# Cap_Array_100p_16u.net
KiCad netlist of a schematic drawn in Altium Designer
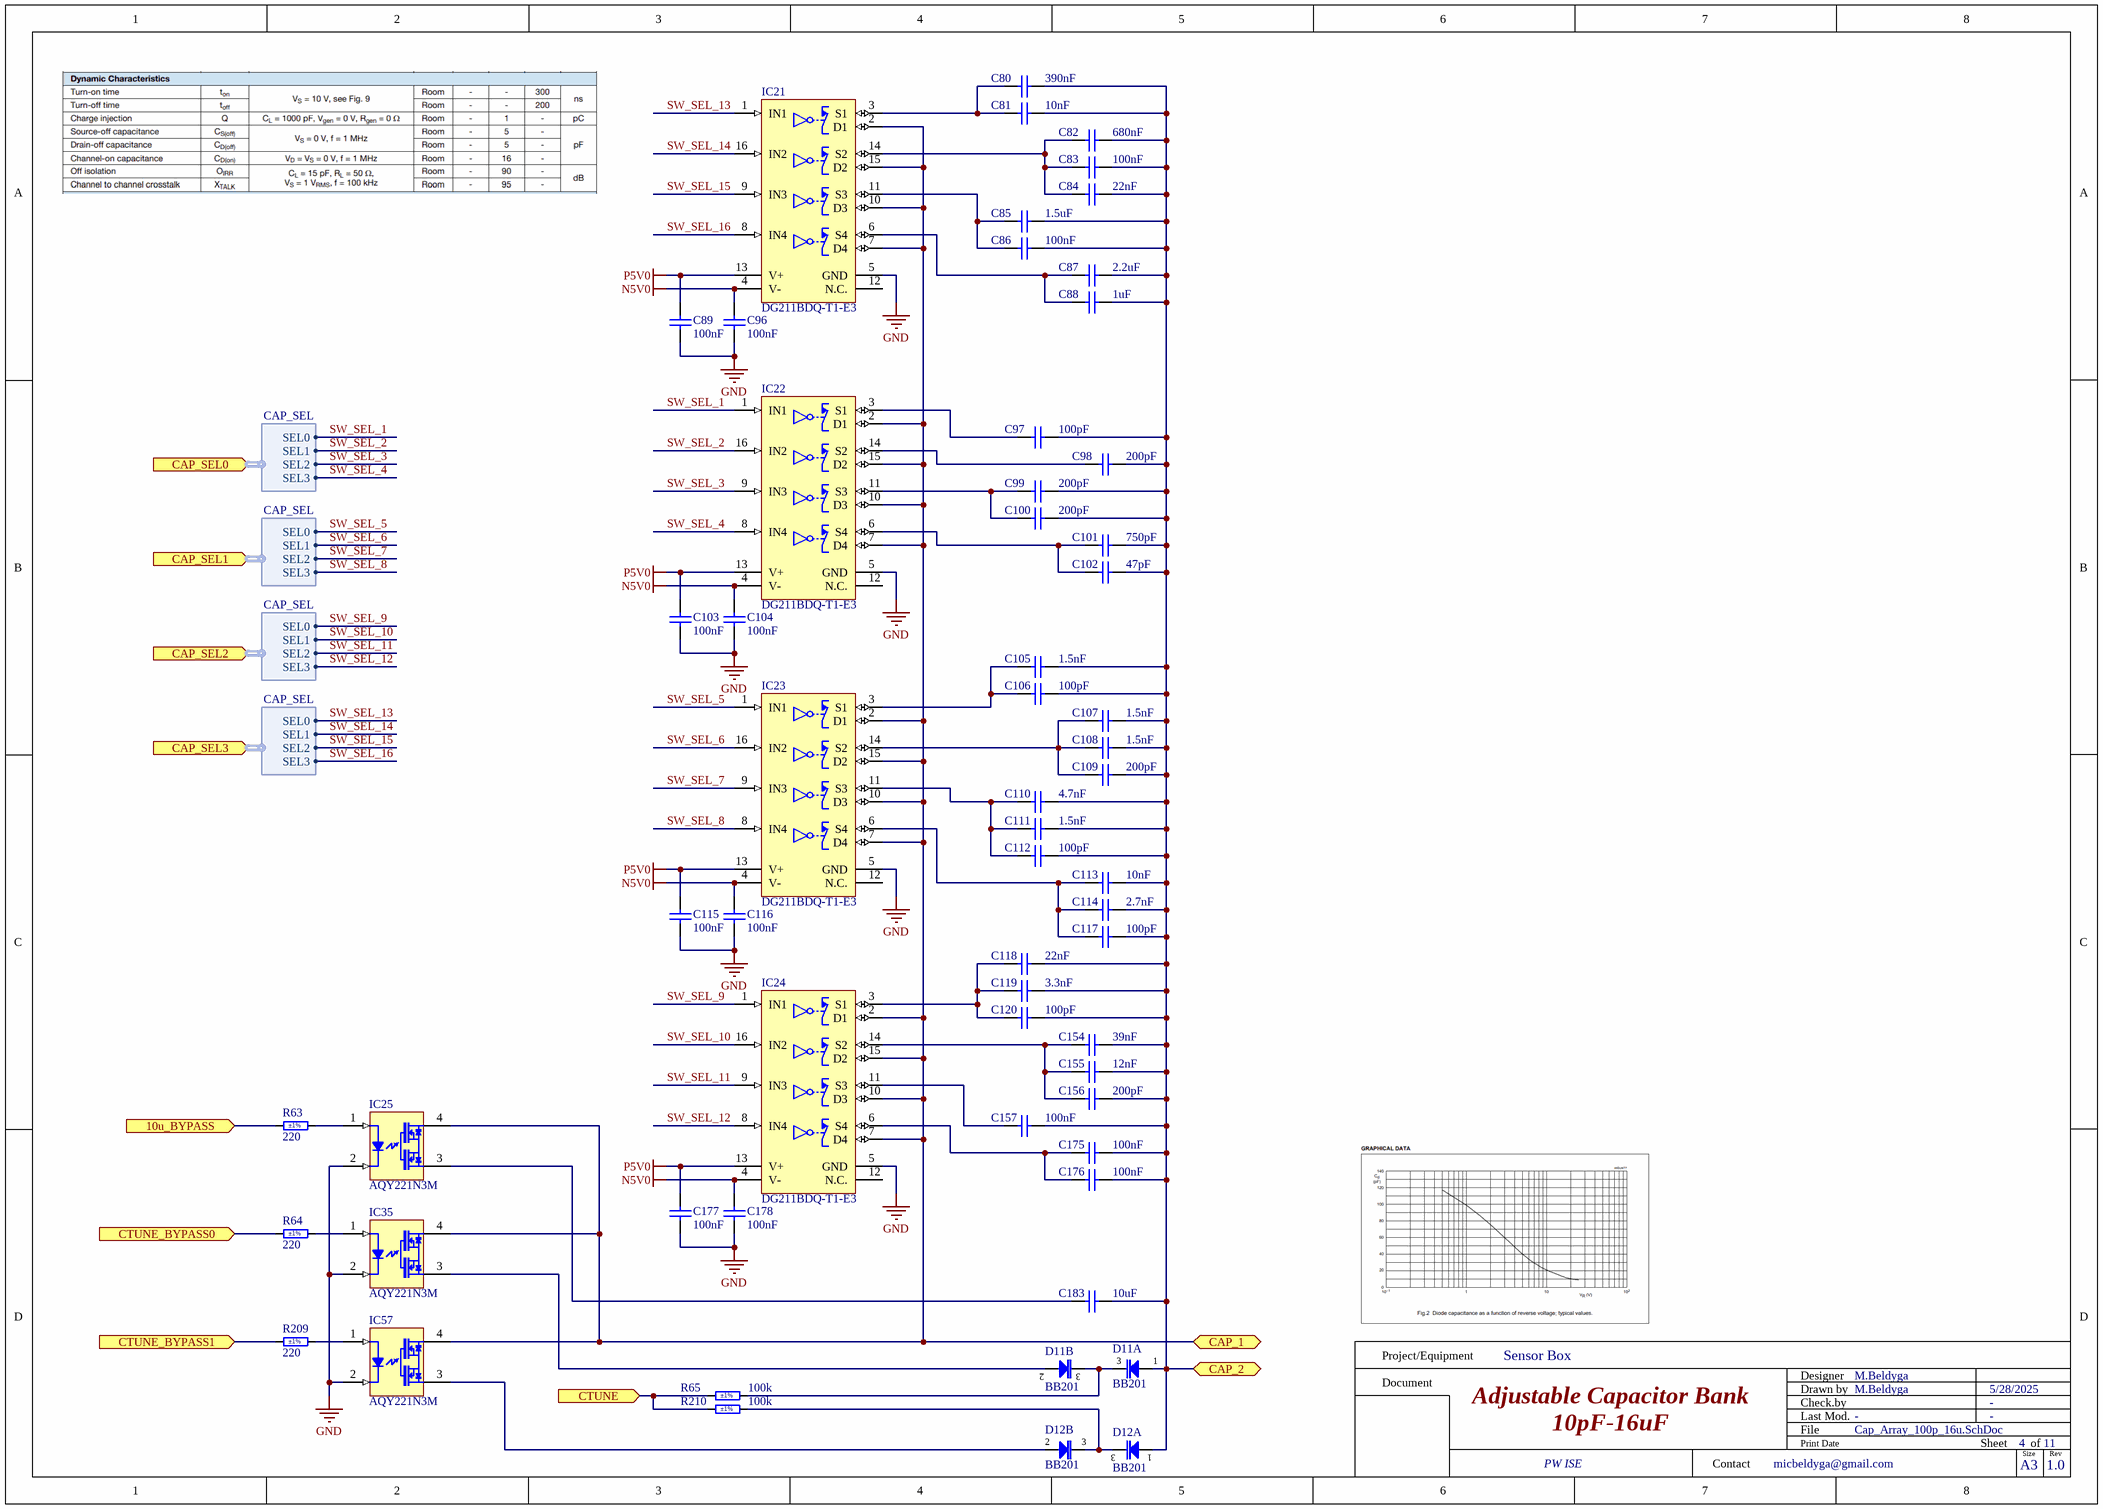
[diagram p0: Cap_Array_100p_16u.SchDoc]

(export (version "E")
  (design (tool "Eeschema 10.0.6"))
  (components
    (comp (ref "C80")
      (value "390nF")
      (footprint "CAPC1608X90N")
      (description "Cap Ceramic 0.39uF 16V X7R 5% Pad SMD 0603 125C T/R")
      (fields
        (field (name "MANUFACTURER") "KEMET")
        (field (name "MANUFACTURER PART NUMBER") "C0603C394J4RACTU")
      )
      (libsource (lib "mb") (part "0603 390nF 16V"))
    )
    (comp (ref "C81")
      (value "10nF")
      (footprint "CAPC1005X55N")
      (description "Non-polarised capacitor")
      (fields
        (field (name "PART NUMBER") "CC0402_10NF_16V_10%_X7R")
        (field (name "VOLTAGE") "16V")
        (field (name "AUTHOR") "CERN DEM JLC")
      )
      (libsource (lib "Capacitors") (part "Capacitor - non polarized"))
    )
    (comp (ref "C82")
      (value "680nF")
      (footprint "CAPC1608X90N")
      (description "Surface Mount Ceramic Multilayer Capacitor 0.68uF 5% X7R 16V 0603 Paper T/R")
      (fields
        (field (name "MANUFACTURER") "Yageo")
        (field (name "MANUFACTURER PART NUMBER") "CC0603JRX7R7BB684")
      )
      (libsource (lib "mb") (part "0603 680nF 16V"))
    )
    (comp (ref "C83")
      (value "100nF")
      (footprint "CAPC1005X55N")
      (description "Non-polarised capacitor")
      (fields
        (field (name "PART NUMBER") "CC0402_100NF_50V_10%_X7R")
        (field (name "VOLTAGE") "50V")
        (field (name "AUTHOR") "CERN DEM MR")
      )
      (libsource (lib "Capacitors") (part "Capacitor - non polarized"))
    )
    (comp (ref "C84")
      (value "22nF")
      (footprint "CAPC1005X55N")
      (description "Non-polarised capacitor")
      (fields
        (field (name "PART NUMBER") "CC0402_22NF_50V_5%_X7R")
        (field (name "VOLTAGE") "50V")
        (field (name "AUTHOR") "CERN DEM BC")
      )
      (libsource (lib "Capacitors") (part "Capacitor - non polarized"))
    )
    (comp (ref "C85")
      (value "1.5uF")
      (footprint "CAPC2012X95N")
      (description "Multilayer Ceramic Capacitors MLCC - SMD/SMT 16V 1.5uF X7R 0805 5% AEC-Q200")
      (fields
        (field (name "MANUFACTURER") "KEMET")
        (field (name "MANUFACTURER PART NUMBER") "C0805C155J4RECAUTO")
      )
      (libsource (lib "mb") (part "0805 1.5uF 16V"))
    )
    (comp (ref "C86")
      (value "100nF")
      (footprint "CAPC1005X55N")
      (description "Non-polarised capacitor")
      (fields
        (field (name "PART NUMBER") "CC0402_100NF_50V_10%_X7R")
        (field (name "VOLTAGE") "50V")
        (field (name "AUTHOR") "CERN DEM MR")
      )
      (libsource (lib "Capacitors") (part "Capacitor - non polarized"))
    )
    (comp (ref "C87")
      (value "2.2uF")
      (footprint "CAPC2012X95N")
      (fields
        (field (name "MANUFACTURER") "KEMET")
        (field (name "MANUFACTURER PART NUMBER") "C0805C225J4RECTU")
      )
      (libsource (lib "mb") (part "0805 2.2uF 16V"))
    )
    (comp (ref "C88")
      (value "1uF")
      (footprint "CAPC1608X90N")
      (description "SMD Multilayer Ceramic Capacitor, 1 ï¿½F, 16 V, 0603 [1608 Metric], ï¿½ 5%, X7R")
      (fields
        (field (name "MANUFACTURER") "Yageo")
        (field (name "MANUFACTURER PART NUMBER") "CC0603JRX7R7BB105")
      )
      (libsource (lib "mb") (part "0603 1uF 16V"))
    )
    (comp (ref "C89")
      (value "100nF")
      (footprint "CAPC1005X55N")
      (description "Non-polarised capacitor")
      (fields
        (field (name "PART NUMBER") "CC0402_100NF_50V_10%_X7R")
        (field (name "VOLTAGE") "50V")
        (field (name "AUTHOR") "CERN DEM MR")
      )
      (libsource (lib "Capacitors") (part "Capacitor - non polarized"))
    )
    (comp (ref "C96")
      (value "100nF")
      (footprint "CAPC1005X55N")
      (description "Non-polarised capacitor")
      (fields
        (field (name "PART NUMBER") "CC0402_100NF_50V_10%_X7R")
        (field (name "VOLTAGE") "50V")
        (field (name "AUTHOR") "CERN DEM MR")
      )
      (libsource (lib "Capacitors") (part "Capacitor - non polarized"))
    )
    (comp (ref "C97")
      (value "100pF")
      (footprint "CAPC1005X55N")
      (description "Non-polarised capacitor")
      (fields
        (field (name "PART NUMBER") "CC0402_100PF_25V_1%_C0G")
        (field (name "VOLTAGE") "25V")
        (field (name "AUTHOR") "CERN DEM HF")
      )
      (libsource (lib "Capacitors") (part "Capacitor - non polarized"))
    )
    (comp (ref "C98")
      (value "200pF")
      (footprint "CAPC1005X55N")
      (description "Multilayer Ceramic Capacitor, 200 pF, 50 V, ï¿½ 1%, C0G (NP0), 0402 [1005 Metric]")
      (fields
        (field (name "MANUFACTURER") "Murata")
        (field (name "MANUFACTURER PART NUMBER") "GCM1555C1H201FA16D")
      )
      (libsource (lib "mb") (part "0402 200pF 50V"))
    )
    (comp (ref "C99")
      (value "200pF")
      (footprint "CAPC1005X55N")
      (description "Multilayer Ceramic Capacitor, 200 pF, 50 V, ï¿½ 1%, C0G (NP0), 0402 [1005 Metric]")
      (fields
        (field (name "MANUFACTURER") "Murata")
        (field (name "MANUFACTURER PART NUMBER") "GCM1555C1H201FA16D")
      )
      (libsource (lib "mb") (part "0402 200pF 50V"))
    )
    (comp (ref "C100")
      (value "200pF")
      (footprint "CAPC1005X55N")
      (description "Multilayer Ceramic Capacitor, 200 pF, 50 V, ï¿½ 1%, C0G (NP0), 0402 [1005 Metric]")
      (fields
        (field (name "MANUFACTURER") "Murata")
        (field (name "MANUFACTURER PART NUMBER") "GCM1555C1H201FA16D")
      )
      (libsource (lib "mb") (part "0402 200pF 50V"))
    )
    (comp (ref "C101")
      (value "750pF")
      (footprint "CAPC1005X55N")
      (description "Cap Auto-grade 750PF 50VDC C0G 1% SMD 0402")
      (fields
        (field (name "MANUFACTURER") "Murata")
        (field (name "MANUFACTURER PART NUMBER") "GCM1555C1H751FA16D")
      )
      (libsource (lib "mb") (part "0402 750pF 50V"))
    )
    (comp (ref "C102")
      (value "47pF")
      (footprint "CAPC1005X55N")
      (description "Non-polarised capacitor")
      (fields
        (field (name "PART NUMBER") "CC0402_47PF_50V_1%_C0G_MURATA_GJM1555C1H470FB01D")
        (field (name "VOLTAGE") "50V")
        (field (name "AUTHOR") "CERN DEM BC")
      )
      (libsource (lib "Capacitors") (part "Capacitor - non polarized"))
    )
    (comp (ref "C103")
      (value "100nF")
      (footprint "CAPC1005X55N")
      (description "Non-polarised capacitor")
      (fields
        (field (name "PART NUMBER") "CC0402_100NF_50V_10%_X7R")
        (field (name "VOLTAGE") "50V")
        (field (name "AUTHOR") "CERN DEM MR")
      )
      (libsource (lib "Capacitors") (part "Capacitor - non polarized"))
    )
    (comp (ref "C104")
      (value "100nF")
      (footprint "CAPC1005X55N")
      (description "Non-polarised capacitor")
      (fields
        (field (name "PART NUMBER") "CC0402_100NF_50V_10%_X7R")
        (field (name "VOLTAGE") "50V")
        (field (name "AUTHOR") "CERN DEM MR")
      )
      (libsource (lib "Capacitors") (part "Capacitor - non polarized"))
    )
    (comp (ref "C105")
      (value "1.5nF")
      (footprint "CAPC1005X55N")
      (fields
        (field (name "MANUFACTURER") "KEMET")
        (field (name "MANUFACTURER PART NUMBER") "C0402C152F5GECAUTO")
      )
      (libsource (lib "mb") (part "0402 1.5nF 50V"))
    )
    (comp (ref "C106")
      (value "100pF")
      (footprint "CAPC1005X55N")
      (description "Non-polarised capacitor")
      (fields
        (field (name "PART NUMBER") "CC0402_100PF_25V_1%_C0G")
        (field (name "VOLTAGE") "25V")
        (field (name "AUTHOR") "CERN DEM HF")
      )
      (libsource (lib "Capacitors") (part "Capacitor - non polarized"))
    )
    (comp (ref "C107")
      (value "1.5nF")
      (footprint "CAPC1005X55N")
      (fields
        (field (name "MANUFACTURER") "KEMET")
        (field (name "MANUFACTURER PART NUMBER") "C0402C152F5GECAUTO")
      )
      (libsource (lib "mb") (part "0402 1.5nF 50V"))
    )
    (comp (ref "C108")
      (value "1.5nF")
      (footprint "CAPC1005X55N")
      (fields
        (field (name "MANUFACTURER") "KEMET")
        (field (name "MANUFACTURER PART NUMBER") "C0402C152F5GECAUTO")
      )
      (libsource (lib "mb") (part "0402 1.5nF 50V"))
    )
    (comp (ref "C109")
      (value "200pF")
      (footprint "CAPC1005X55N")
      (description "Multilayer Ceramic Capacitor, 200 pF, 50 V, ï¿½ 1%, C0G (NP0), 0402 [1005 Metric]")
      (fields
        (field (name "MANUFACTURER") "Murata")
        (field (name "MANUFACTURER PART NUMBER") "GCM1555C1H201FA16D")
      )
      (libsource (lib "mb") (part "0402 200pF 50V"))
    )
    (comp (ref "C110")
      (value "4.7nF")
      (footprint "CAPC1608X90N")
      (description "Cap Ceramic 0.0047uF 50V C0G 1% Pad SMD 0603 125°C Automotive T/R")
      (fields
        (field (name "MANUFACTURER") "Murata")
        (field (name "MANUFACTURER PART NUMBER") "GCM1885C1H472FA16D")
      )
      (libsource (lib "mb") (part "0603 4.7nF 50V"))
    )
    (comp (ref "C111")
      (value "1.5nF")
      (footprint "CAPC1005X55N")
      (fields
        (field (name "MANUFACTURER") "KEMET")
        (field (name "MANUFACTURER PART NUMBER") "C0402C152F5GECAUTO")
      )
      (libsource (lib "mb") (part "0402 1.5nF 50V"))
    )
    (comp (ref "C112")
      (value "100pF")
      (footprint "CAPC1005X55N")
      (description "Non-polarised capacitor")
      (fields
        (field (name "PART NUMBER") "CC0402_100PF_25V_1%_C0G")
        (field (name "VOLTAGE") "25V")
        (field (name "AUTHOR") "CERN DEM HF")
      )
      (libsource (lib "Capacitors") (part "Capacitor - non polarized"))
    )
    (comp (ref "C113")
      (value "10nF")
      (footprint "CAPC1608X90N")
      (description "Multilayer Ceramic Capacitors MLCC - SMD/SMT 25V 0.01uF C0G 0603 1% AEC-Q200")
      (fields
        (field (name "MANUFACTURER") "KEMET")
        (field (name "MANUFACTURER PART NUMBER") "C0603C103F3GECAUTO")
      )
      (libsource (lib "mb") (part "0603 10nF 25V"))
    )
    (comp (ref "C114")
      (value "2.7nF")
      (footprint "CAPC1608X90N")
      (description "Powerrain/Safety for Automotive AEC-Q200 Up to 125C Reflow soldering Flow soldering")
      (fields
        (field (name "MANUFACTURER") "Murata")
        (field (name "MANUFACTURER PART NUMBER") "GCM1885C1H272FA16J")
      )
      (libsource (lib "mb") (part "0603 2.7nF 50V"))
    )
    (comp (ref "C115")
      (value "100nF")
      (footprint "CAPC1005X55N")
      (description "Non-polarised capacitor")
      (fields
        (field (name "PART NUMBER") "CC0402_100NF_50V_10%_X7R")
        (field (name "VOLTAGE") "50V")
        (field (name "AUTHOR") "CERN DEM MR")
      )
      (libsource (lib "Capacitors") (part "Capacitor - non polarized"))
    )
    (comp (ref "C116")
      (value "100nF")
      (footprint "CAPC1005X55N")
      (description "Non-polarised capacitor")
      (fields
        (field (name "PART NUMBER") "CC0402_100NF_50V_10%_X7R")
        (field (name "VOLTAGE") "50V")
        (field (name "AUTHOR") "CERN DEM MR")
      )
      (libsource (lib "Capacitors") (part "Capacitor - non polarized"))
    )
    (comp (ref "C117")
      (value "100pF")
      (footprint "CAPC1005X55N")
      (description "Non-polarised capacitor")
      (fields
        (field (name "PART NUMBER") "CC0402_100PF_25V_1%_C0G")
        (field (name "VOLTAGE") "25V")
        (field (name "AUTHOR") "CERN DEM HF")
      )
      (libsource (lib "Capacitors") (part "Capacitor - non polarized"))
    )
    (comp (ref "C118")
      (value "22nF")
      (footprint "CAPC2012X95N")
      (description "0805 50V C0G 0.022uF 1% Automotive grade multilayer ceramic capacitor")
      (fields
        (field (name "MANUFACTURER") "Murata")
        (field (name "MANUFACTURER PART NUMBER") "GCM21B5C1H223FA16L")
      )
      (libsource (lib "mb") (part "0805 22nF 50V"))
    )
    (comp (ref "C119")
      (value "3.3nF")
      (footprint "CAPC1608X90N")
      (description "Cap Ceramic 0.0033uF 50V C0G 1% Pad SMD 0603 125°C Automotive T/R")
      (fields
        (field (name "MANUFACTURER") "Murata")
        (field (name "MANUFACTURER PART NUMBER") "GCM1885C1H332FA16D")
      )
      (libsource (lib "mb") (part "0603 3.3nF 50V"))
    )
    (comp (ref "C120")
      (value "100pF")
      (footprint "CAPC1005X55N")
      (description "Non-polarised capacitor")
      (fields
        (field (name "PART NUMBER") "CC0402_100PF_25V_1%_C0G")
        (field (name "VOLTAGE") "25V")
        (field (name "AUTHOR") "CERN DEM HF")
      )
      (libsource (lib "Capacitors") (part "Capacitor - non polarized"))
    )
    (comp (ref "C154")
      (value "39nF")
      (footprint "CAPC2012X95N")
      (description "Multilayer Ceramic Capacitors MLCC - SMD/SMT 0805 C0G 39000pF 2% 100VDC")
      (fields
        (field (name "MANUFACTURER") "Murata")
        (field (name "MANUFACTURER PART NUMBER") "GRM2195C2A393GE01J")
      )
      (libsource (lib "mb") (part "0805 39nF 100V"))
    )
    (comp (ref "C155")
      (value "12nF")
      (footprint "CAPC1608X90N")
      (description "Cap Ceramic 0.012uF 25V C0G 1% Pad SMD 0603 125°C Extreme Low ESR T/R")
      (fields
        (field (name "MANUFACTURER") "KEMET")
        (field (name "MANUFACTURER PART NUMBER") "C0603C123F3GACTU")
      )
      (libsource (lib "mb") (part "0603 12nF 25V"))
    )
    (comp (ref "C156")
      (value "200pF")
      (footprint "CAPC1005X55N")
      (description "Multilayer Ceramic Capacitor, 200 pF, 50 V, ï¿½ 1%, C0G (NP0), 0402 [1005 Metric]")
      (fields
        (field (name "MANUFACTURER") "Murata")
        (field (name "MANUFACTURER PART NUMBER") "GCM1555C1H201FA16D")
      )
      (libsource (lib "mb") (part "0402 200pF 50V"))
    )
    (comp (ref "C157")
      (value "100nF")
      (footprint "CAPC1810X06N")
      (description "Cap Cer 0.1UF 50V C0G/NP0 0704")
      (fields
        (field (name "MANUFACTURER") "Murata")
        (field (name "MANUFACTURER PART NUMBER") "GRMJN65C1H104GE01J")
      )
      (libsource (lib "mb") (part "0704 100nF 50V"))
    )
    (comp (ref "C175")
      (value "100nF")
      (footprint "CAPC1810X06N")
      (description "Cap Cer 0.1UF 50V C0G/NP0 0704")
      (fields
        (field (name "MANUFACTURER") "Murata")
        (field (name "MANUFACTURER PART NUMBER") "GRMJN65C1H104GE01J")
      )
      (libsource (lib "mb") (part "0704 100nF 50V"))
    )
    (comp (ref "C176")
      (value "100nF")
      (footprint "CAPC1810X06N")
      (description "Cap Cer 0.1UF 50V C0G/NP0 0704")
      (fields
        (field (name "MANUFACTURER") "Murata")
        (field (name "MANUFACTURER PART NUMBER") "GRMJN65C1H104GE01J")
      )
      (libsource (lib "mb") (part "0704 100nF 50V"))
    )
    (comp (ref "C177")
      (value "100nF")
      (footprint "CAPC1005X55N")
      (description "Non-polarised capacitor")
      (fields
        (field (name "PART NUMBER") "CC0402_100NF_50V_10%_X7R")
        (field (name "VOLTAGE") "50V")
        (field (name "AUTHOR") "CERN DEM MR")
      )
      (libsource (lib "Capacitors") (part "Capacitor - non polarized"))
    )
    (comp (ref "C178")
      (value "100nF")
      (footprint "CAPC1005X55N")
      (description "Non-polarised capacitor")
      (fields
        (field (name "PART NUMBER") "CC0402_100NF_50V_10%_X7R")
        (field (name "VOLTAGE") "50V")
        (field (name "AUTHOR") "CERN DEM MR")
      )
      (libsource (lib "Capacitors") (part "Capacitor - non polarized"))
    )
    (comp (ref "C183")
      (value "10uF")
      (footprint "CAPC2012X95N")
      (description "Multilayer Ceramic Capacitors MLCC - SMD/SMT 10V 10uF X7R 0805 5% AEC-Q200")
      (fields
        (field (name "MANUFACTURER") "KEMET")
        (field (name "MANUFACTURER PART NUMBER") "C0805C106J8RACAUTO")
      )
      (libsource (lib "mb") (part "0805 10uF 16V"))
    )
    (comp (ref "D11")
      (value "BB201")
      (footprint "SOT95P230X110-3N")
      (description "Dual Common Cathode Varicap Diodes")
      (fields
        (field (name "VOLTAGE") "15V")
        (field (name "POWER") "20mA")
        (field (name "AUTHOR") "CERN DEM JLC")
      )
      (libsource (lib "") (part "Diode Varicap x2 A1C3_A2C3_1"))
    )
    (comp (ref "D12")
      (value "BB201")
      (footprint "SOT95P230X110-3N")
      (description "Dual Common Cathode Varicap Diodes")
      (fields
        (field (name "VOLTAGE") "15V")
        (field (name "POWER") "20mA")
        (field (name "AUTHOR") "CERN DEM JLC")
      )
      (libsource (lib "") (part "Diode Varicap x2 A1C3_A2C3_2"))
    )
    (comp (ref "IC21")
      (value "DG211BDQ-T1-E3")
      (footprint "SOP65P640X120-16N")
      (description "DG211B Series SPST 22 V 50 Ohm Surface Mount Improved Analog Switch - TSSOP-16")
      (fields (field (name "MANUFACTURER") "Vishay Siliconix"))
      (libsource (lib "mb") (part "DG211BDQ-T1-E3"))
    )
    (comp (ref "IC22")
      (value "DG211BDQ-T1-E3")
      (footprint "SOP65P640X120-16N")
      (description "DG211B Series SPST 22 V 50 Ohm Surface Mount Improved Analog Switch - TSSOP-16")
      (fields (field (name "MANUFACTURER") "Vishay Siliconix"))
      (libsource (lib "mb") (part "DG211BDQ-T1-E3"))
    )
    (comp (ref "IC23")
      (value "DG211BDQ-T1-E3")
      (footprint "SOP65P640X120-16N")
      (description "DG211B Series SPST 22 V 50 Ohm Surface Mount Improved Analog Switch - TSSOP-16")
      (fields (field (name "MANUFACTURER") "Vishay Siliconix"))
      (libsource (lib "mb") (part "DG211BDQ-T1-E3"))
    )
    (comp (ref "IC24")
      (value "DG211BDQ-T1-E3")
      (footprint "SOP65P640X120-16N")
      (description "DG211B Series SPST 22 V 50 Ohm Surface Mount Improved Analog Switch - TSSOP-16")
      (fields (field (name "MANUFACTURER") "Vishay Siliconix"))
      (libsource (lib "mb") (part "DG211BDQ-T1-E3"))
    )
    (comp (ref "IC25")
      (value "AQY221N3M")
      (footprint "PANASONIC_AQY22(SON)")
      (description "PhotoMOS Relay")
      (fields (field (name "MANUFACTURER") "PANASONIC") (field (name "AUTHOR") "CERN DEM JLC"))
      (libsource (lib "ICs And Semiconductors") (part "PhotoMOS Relay x1 Type5_a"))
    )
    (comp (ref "IC35")
      (value "AQY221N3M")
      (footprint "PANASONIC_AQY22(SON)")
      (description "PhotoMOS Relay")
      (fields (field (name "MANUFACTURER") "PANASONIC") (field (name "AUTHOR") "CERN DEM JLC"))
      (libsource (lib "ICs And Semiconductors") (part "PhotoMOS Relay x1 Type5_a"))
    )
    (comp (ref "IC57")
      (value "AQY221N3M")
      (footprint "PANASONIC_AQY22(SON)")
      (description "PhotoMOS Relay")
      (fields (field (name "MANUFACTURER") "PANASONIC") (field (name "AUTHOR") "CERN DEM JLC"))
      (libsource (lib "ICs And Semiconductors") (part "PhotoMOS Relay x1 Type5_a"))
    )
    (comp (ref "R63")
      (value "220")
      (footprint "RESC1005X40N")
      (description "Resistor - 1%")
      (fields
        (field (name "TOLERANCE") "±1%")
        (field (name "PART NUMBER") "R0402_220R_1%_0.0625W_100PPM")
        (field (name "POWER") "0.0625W")
        (field (name "AUTHOR") "CERN DEM JLC")
      )
      (libsource (lib "Resistors") (part "Resistor - 1%"))
    )
    (comp (ref "R64")
      (value "220")
      (footprint "RESC1005X40N")
      (description "Resistor - 1%")
      (fields
        (field (name "TOLERANCE") "±1%")
        (field (name "PART NUMBER") "R0402_220R_1%_0.0625W_100PPM")
        (field (name "POWER") "0.0625W")
        (field (name "AUTHOR") "CERN DEM JLC")
      )
      (libsource (lib "Resistors") (part "Resistor - 1%"))
    )
    (comp (ref "R65")
      (value "100k")
      (footprint "RESC1005X40N")
      (description "Resistor - 1%")
      (fields
        (field (name "TOLERANCE") "±1%")
        (field (name "PART NUMBER") "R0402_100K_1%_0.0625W_100PPM")
        (field (name "POWER") "0.0625W")
        (field (name "AUTHOR") "CERN DEM JLC")
      )
      (libsource (lib "Resistors") (part "Resistor - 1%"))
    )
    (comp (ref "R209")
      (value "220")
      (footprint "RESC1005X40N")
      (description "Resistor - 1%")
      (fields
        (field (name "TOLERANCE") "±1%")
        (field (name "PART NUMBER") "R0402_220R_1%_0.0625W_100PPM")
        (field (name "POWER") "0.0625W")
        (field (name "AUTHOR") "CERN DEM JLC")
      )
      (libsource (lib "Resistors") (part "Resistor - 1%"))
    )
    (comp (ref "R210")
      (value "100k")
      (footprint "RESC1005X40N")
      (description "Resistor - 1%")
      (fields
        (field (name "TOLERANCE") "±1%")
        (field (name "PART NUMBER") "R0402_100K_1%_0.0625W_100PPM")
        (field (name "POWER") "0.0625W")
        (field (name "AUTHOR") "CERN DEM JLC")
      )
      (libsource (lib "Resistors") (part "Resistor - 1%"))
    )
  )
  (nets
    (net (code "2") (name "/10u_BYPASS") (class "Default")
      (node (ref "R63") (pin "1") (pinfunction "1_1") (pintype "passive"))
    )
    (net (code "3") (name "/CAP_1") (class "Default")
      (node (ref "IC21") (pin "10") (pinfunction "D3_10") (pintype "bidirectional"))
      (node (ref "IC21") (pin "15") (pinfunction "D2_15") (pintype "bidirectional"))
      (node (ref "IC21") (pin "2") (pinfunction "D1_2") (pintype "bidirectional"))
      (node (ref "IC21") (pin "7") (pinfunction "D4_7") (pintype "bidirectional"))
      (node (ref "IC22") (pin "10") (pinfunction "D3_10") (pintype "bidirectional"))
      (node (ref "IC22") (pin "15") (pinfunction "D2_15") (pintype "bidirectional"))
      (node (ref "IC22") (pin "2") (pinfunction "D1_2") (pintype "bidirectional"))
      (node (ref "IC22") (pin "7") (pinfunction "D4_7") (pintype "bidirectional"))
      (node (ref "IC23") (pin "10") (pinfunction "D3_10") (pintype "bidirectional"))
      (node (ref "IC23") (pin "15") (pinfunction "D2_15") (pintype "bidirectional"))
      (node (ref "IC23") (pin "2") (pinfunction "D1_2") (pintype "bidirectional"))
      (node (ref "IC23") (pin "7") (pinfunction "D4_7") (pintype "bidirectional"))
      (node (ref "IC24") (pin "10") (pinfunction "D3_10") (pintype "bidirectional"))
      (node (ref "IC24") (pin "15") (pinfunction "D2_15") (pintype "bidirectional"))
      (node (ref "IC24") (pin "2") (pinfunction "D1_2") (pintype "bidirectional"))
      (node (ref "IC24") (pin "7") (pinfunction "D4_7") (pintype "bidirectional"))
      (node (ref "IC25") (pin "4") (pinfunction "E_4") (pintype "open_emitter"))
      (node (ref "IC35") (pin "4") (pinfunction "E_4") (pintype "open_emitter"))
      (node (ref "IC57") (pin "4") (pinfunction "E_4") (pintype "open_emitter"))
    )
    (net (code "4") (name "/CAP_2") (class "Default")
      (node (ref "C100") (pin "1") (pinfunction "1_1") (pintype "passive"))
      (node (ref "C101") (pin "1") (pinfunction "1_1") (pintype "passive"))
      (node (ref "C102") (pin "2") (pinfunction "2_2") (pintype "passive"))
      (node (ref "C105") (pin "1") (pinfunction "1_1") (pintype "passive"))
      (node (ref "C106") (pin "2") (pinfunction "2_2") (pintype "passive"))
      (node (ref "C107") (pin "1") (pinfunction "1_1") (pintype "passive"))
      (node (ref "C108") (pin "1") (pinfunction "1_1") (pintype "passive"))
      (node (ref "C109") (pin "1") (pinfunction "1_1") (pintype "passive"))
      (node (ref "C110") (pin "1") (pinfunction "1_1") (pintype "passive"))
      (node (ref "C111") (pin "1") (pinfunction "1_1") (pintype "passive"))
      (node (ref "C112") (pin "2") (pinfunction "2_2") (pintype "passive"))
      (node (ref "C113") (pin "1") (pinfunction "1_1") (pintype "passive"))
      (node (ref "C114") (pin "1") (pinfunction "1_1") (pintype "passive"))
      (node (ref "C117") (pin "2") (pinfunction "2_2") (pintype "passive"))
      (node (ref "C118") (pin "1") (pinfunction "1_1") (pintype "passive"))
      (node (ref "C119") (pin "1") (pinfunction "1_1") (pintype "passive"))
      (node (ref "C120") (pin "2") (pinfunction "2_2") (pintype "passive"))
      (node (ref "C154") (pin "1") (pinfunction "1_1") (pintype "passive"))
      (node (ref "C155") (pin "1") (pinfunction "1_1") (pintype "passive"))
      (node (ref "C156") (pin "1") (pinfunction "1_1") (pintype "passive"))
      (node (ref "C157") (pin "1") (pinfunction "1_1") (pintype "passive"))
      (node (ref "C175") (pin "1") (pinfunction "1_1") (pintype "passive"))
      (node (ref "C176") (pin "1") (pinfunction "1_1") (pintype "passive"))
      (node (ref "C183") (pin "1") (pinfunction "1_1") (pintype "passive"))
      (node (ref "C80") (pin "1") (pinfunction "1_1") (pintype "passive"))
      (node (ref "C81") (pin "2") (pinfunction "2_2") (pintype "passive"))
      (node (ref "C82") (pin "1") (pinfunction "1_1") (pintype "passive"))
      (node (ref "C83") (pin "1") (pinfunction "1_1") (pintype "passive"))
      (node (ref "C84") (pin "2") (pinfunction "2_2") (pintype "passive"))
      (node (ref "C85") (pin "1") (pinfunction "1_1") (pintype "passive"))
      (node (ref "C86") (pin "1") (pinfunction "1_1") (pintype "passive"))
      (node (ref "C87") (pin "1") (pinfunction "1_1") (pintype "passive"))
      (node (ref "C88") (pin "1") (pinfunction "1_1") (pintype "passive"))
      (node (ref "C97") (pin "2") (pinfunction "2_2") (pintype "passive"))
      (node (ref "C98") (pin "1") (pinfunction "1_1") (pintype "passive"))
      (node (ref "C99") (pin "1") (pinfunction "1_1") (pintype "passive"))
      (node (ref "D11") (pin "1") (pinfunction "A_1") (pintype "passive"))
      (node (ref "D12") (pin "1") (pinfunction "A_1") (pintype "passive"))
    )
    (net (code "5") (name "/CTUNE") (class "Default")
      (node (ref "R210") (pin "2") (pinfunction "2_2") (pintype "passive"))
      (node (ref "R65") (pin "2") (pinfunction "2_2") (pintype "passive"))
    )
    (net (code "6") (name "/CTUNE_BYPASS0") (class "Default")
      (node (ref "R64") (pin "1") (pinfunction "1_1") (pintype "passive"))
    )
    (net (code "7") (name "/CTUNE_BYPASS1") (class "Default")
      (node (ref "R209") (pin "1") (pinfunction "1_1") (pintype "passive"))
    )
    (net (code "8") (name "/SW_SEL_1") (class "Default")
      (node (ref "IC22") (pin "1") (pinfunction "IN1_1") (pintype "input"))
    )
    (net (code "9") (name "/SW_SEL_2") (class "Default")
      (node (ref "IC22") (pin "16") (pinfunction "IN2_16") (pintype "input"))
    )
    (net (code "10") (name "/SW_SEL_3") (class "Default")
      (node (ref "IC22") (pin "9") (pinfunction "IN3_9") (pintype "input"))
    )
    (net (code "11") (name "/SW_SEL_4") (class "Default")
      (node (ref "IC22") (pin "8") (pinfunction "IN4_8") (pintype "input"))
    )
    (net (code "12") (name "/SW_SEL_5") (class "Default")
      (node (ref "IC23") (pin "1") (pinfunction "IN1_1") (pintype "input"))
    )
    (net (code "13") (name "/SW_SEL_6") (class "Default")
      (node (ref "IC23") (pin "16") (pinfunction "IN2_16") (pintype "input"))
    )
    (net (code "14") (name "/SW_SEL_7") (class "Default")
      (node (ref "IC23") (pin "9") (pinfunction "IN3_9") (pintype "input"))
    )
    (net (code "15") (name "/SW_SEL_8") (class "Default")
      (node (ref "IC23") (pin "8") (pinfunction "IN4_8") (pintype "input"))
    )
    (net (code "16") (name "/SW_SEL_9") (class "Default")
      (node (ref "IC24") (pin "1") (pinfunction "IN1_1") (pintype "input"))
    )
    (net (code "17") (name "/SW_SEL_10") (class "Default")
      (node (ref "IC24") (pin "16") (pinfunction "IN2_16") (pintype "input"))
    )
    (net (code "18") (name "/SW_SEL_11") (class "Default")
      (node (ref "IC24") (pin "9") (pinfunction "IN3_9") (pintype "input"))
    )
    (net (code "19") (name "/SW_SEL_12") (class "Default")
      (node (ref "IC24") (pin "8") (pinfunction "IN4_8") (pintype "input"))
    )
    (net (code "20") (name "/SW_SEL_13") (class "Default")
      (node (ref "IC21") (pin "1") (pinfunction "IN1_1") (pintype "input"))
    )
    (net (code "21") (name "/SW_SEL_14") (class "Default")
      (node (ref "IC21") (pin "16") (pinfunction "IN2_16") (pintype "input"))
    )
    (net (code "22") (name "/SW_SEL_15") (class "Default")
      (node (ref "IC21") (pin "9") (pinfunction "IN3_9") (pintype "input"))
    )
    (net (code "23") (name "/SW_SEL_16") (class "Default")
      (node (ref "IC21") (pin "8") (pinfunction "IN4_8") (pintype "input"))
    )
    (net (code "25") (name "GND") (class "Default")
      (node (ref "C103") (pin "1") (pinfunction "1_1") (pintype "passive"))
      (node (ref "C104") (pin "1") (pinfunction "1_1") (pintype "passive"))
      (node (ref "C115") (pin "1") (pinfunction "1_1") (pintype "passive"))
      (node (ref "C116") (pin "1") (pinfunction "1_1") (pintype "passive"))
      (node (ref "C177") (pin "1") (pinfunction "1_1") (pintype "passive"))
      (node (ref "C178") (pin "1") (pinfunction "1_1") (pintype "passive"))
      (node (ref "C89") (pin "1") (pinfunction "1_1") (pintype "passive"))
      (node (ref "C96") (pin "1") (pinfunction "1_1") (pintype "passive"))
      (node (ref "IC21") (pin "5") (pinfunction "GND_5") (pintype "power_in"))
      (node (ref "IC22") (pin "5") (pinfunction "GND_5") (pintype "power_in"))
      (node (ref "IC23") (pin "5") (pinfunction "GND_5") (pintype "power_in"))
      (node (ref "IC24") (pin "5") (pinfunction "GND_5") (pintype "power_in"))
      (node (ref "IC25") (pin "2") (pinfunction "K_2") (pintype "input"))
      (node (ref "IC35") (pin "2") (pinfunction "K_2") (pintype "input"))
      (node (ref "IC57") (pin "2") (pinfunction "K_2") (pintype "input"))
    )
    (net (code "26") (name "N5V0") (class "Default")
      (node (ref "C104") (pin "2") (pinfunction "2_2") (pintype "passive"))
      (node (ref "C116") (pin "2") (pinfunction "2_2") (pintype "passive"))
      (node (ref "C178") (pin "2") (pinfunction "2_2") (pintype "passive"))
      (node (ref "C96") (pin "2") (pinfunction "2_2") (pintype "passive"))
      (node (ref "IC21") (pin "4") (pinfunction "V-_4") (pintype "power_in"))
      (node (ref "IC22") (pin "4") (pinfunction "V-_4") (pintype "power_in"))
      (node (ref "IC23") (pin "4") (pinfunction "V-_4") (pintype "power_in"))
      (node (ref "IC24") (pin "4") (pinfunction "V-_4") (pintype "power_in"))
    )
    (net (code "27") (name "Net-(D11A-COMC)") (class "Default")
      (node (ref "D11") (pin "3") (pinfunction "COMC_3") (pintype "passive"))
      (node (ref "R65") (pin "1") (pinfunction "1_1") (pintype "passive"))
    )
    (net (code "28") (name "Net-(D11B-A)") (class "Default")
      (node (ref "D11") (pin "2") (pinfunction "A_2") (pintype "passive"))
      (node (ref "IC35") (pin "3") (pinfunction "C_3") (pintype "open_collector"))
    )
    (net (code "29") (name "Net-(D12A-COMC)") (class "Default")
      (node (ref "D12") (pin "3") (pinfunction "COMC_3") (pintype "passive"))
      (node (ref "R210") (pin "1") (pinfunction "1_1") (pintype "passive"))
    )
    (net (code "30") (name "Net-(D12B-A)") (class "Default")
      (node (ref "D12") (pin "2") (pinfunction "A_2") (pintype "passive"))
      (node (ref "IC57") (pin "3") (pinfunction "C_3") (pintype "open_collector"))
    )
    (net (code "31") (name "Net-(IC21-S1)") (class "Default")
      (node (ref "C80") (pin "2") (pinfunction "2_2") (pintype "passive"))
      (node (ref "C81") (pin "1") (pinfunction "1_1") (pintype "passive"))
      (node (ref "IC21") (pin "3") (pinfunction "S1_3") (pintype "bidirectional"))
    )
    (net (code "32") (name "Net-(IC21-S2)") (class "Default")
      (node (ref "C82") (pin "2") (pinfunction "2_2") (pintype "passive"))
      (node (ref "C83") (pin "2") (pinfunction "2_2") (pintype "passive"))
      (node (ref "C84") (pin "1") (pinfunction "1_1") (pintype "passive"))
      (node (ref "IC21") (pin "14") (pinfunction "S2_14") (pintype "bidirectional"))
    )
    (net (code "33") (name "Net-(IC21-S3)") (class "Default")
      (node (ref "C85") (pin "2") (pinfunction "2_2") (pintype "passive"))
      (node (ref "C86") (pin "2") (pinfunction "2_2") (pintype "passive"))
      (node (ref "IC21") (pin "11") (pinfunction "S3_11") (pintype "bidirectional"))
    )
    (net (code "34") (name "Net-(IC21-S4)") (class "Default")
      (node (ref "C87") (pin "2") (pinfunction "2_2") (pintype "passive"))
      (node (ref "C88") (pin "2") (pinfunction "2_2") (pintype "passive"))
      (node (ref "IC21") (pin "6") (pinfunction "S4_6") (pintype "bidirectional"))
    )
    (net (code "35") (name "Net-(IC22-S1)") (class "Default")
      (node (ref "C97") (pin "1") (pinfunction "1_1") (pintype "passive"))
      (node (ref "IC22") (pin "3") (pinfunction "S1_3") (pintype "bidirectional"))
    )
    (net (code "36") (name "Net-(IC22-S2)") (class "Default")
      (node (ref "C98") (pin "2") (pinfunction "2_2") (pintype "passive"))
      (node (ref "IC22") (pin "14") (pinfunction "S2_14") (pintype "bidirectional"))
    )
    (net (code "37") (name "Net-(IC22-S3)") (class "Default")
      (node (ref "C100") (pin "2") (pinfunction "2_2") (pintype "passive"))
      (node (ref "C99") (pin "2") (pinfunction "2_2") (pintype "passive"))
      (node (ref "IC22") (pin "11") (pinfunction "S3_11") (pintype "bidirectional"))
    )
    (net (code "38") (name "Net-(IC22-S4)") (class "Default")
      (node (ref "C101") (pin "2") (pinfunction "2_2") (pintype "passive"))
      (node (ref "C102") (pin "1") (pinfunction "1_1") (pintype "passive"))
      (node (ref "IC22") (pin "6") (pinfunction "S4_6") (pintype "bidirectional"))
    )
    (net (code "39") (name "Net-(IC23-S1)") (class "Default")
      (node (ref "C105") (pin "2") (pinfunction "2_2") (pintype "passive"))
      (node (ref "C106") (pin "1") (pinfunction "1_1") (pintype "passive"))
      (node (ref "IC23") (pin "3") (pinfunction "S1_3") (pintype "bidirectional"))
    )
    (net (code "40") (name "Net-(IC23-S2)") (class "Default")
      (node (ref "C107") (pin "2") (pinfunction "2_2") (pintype "passive"))
      (node (ref "C108") (pin "2") (pinfunction "2_2") (pintype "passive"))
      (node (ref "C109") (pin "2") (pinfunction "2_2") (pintype "passive"))
      (node (ref "IC23") (pin "14") (pinfunction "S2_14") (pintype "bidirectional"))
    )
    (net (code "41") (name "Net-(IC23-S3)") (class "Default")
      (node (ref "C110") (pin "2") (pinfunction "2_2") (pintype "passive"))
      (node (ref "C111") (pin "2") (pinfunction "2_2") (pintype "passive"))
      (node (ref "C112") (pin "1") (pinfunction "1_1") (pintype "passive"))
      (node (ref "IC23") (pin "11") (pinfunction "S3_11") (pintype "bidirectional"))
    )
    (net (code "42") (name "Net-(IC23-S4)") (class "Default")
      (node (ref "C113") (pin "2") (pinfunction "2_2") (pintype "passive"))
      (node (ref "C114") (pin "2") (pinfunction "2_2") (pintype "passive"))
      (node (ref "C117") (pin "1") (pinfunction "1_1") (pintype "passive"))
      (node (ref "IC23") (pin "6") (pinfunction "S4_6") (pintype "bidirectional"))
    )
    (net (code "43") (name "Net-(IC24-S1)") (class "Default")
      (node (ref "C118") (pin "2") (pinfunction "2_2") (pintype "passive"))
      (node (ref "C119") (pin "2") (pinfunction "2_2") (pintype "passive"))
      (node (ref "C120") (pin "1") (pinfunction "1_1") (pintype "passive"))
      (node (ref "IC24") (pin "3") (pinfunction "S1_3") (pintype "bidirectional"))
    )
    (net (code "44") (name "Net-(IC24-S2)") (class "Default")
      (node (ref "C154") (pin "2") (pinfunction "2_2") (pintype "passive"))
      (node (ref "C155") (pin "2") (pinfunction "2_2") (pintype "passive"))
      (node (ref "C156") (pin "2") (pinfunction "2_2") (pintype "passive"))
      (node (ref "IC24") (pin "14") (pinfunction "S2_14") (pintype "bidirectional"))
    )
    (net (code "45") (name "Net-(IC24-S3)") (class "Default")
      (node (ref "C157") (pin "2") (pinfunction "2_2") (pintype "passive"))
      (node (ref "IC24") (pin "11") (pinfunction "S3_11") (pintype "bidirectional"))
    )
    (net (code "46") (name "Net-(IC24-S4)") (class "Default")
      (node (ref "C175") (pin "2") (pinfunction "2_2") (pintype "passive"))
      (node (ref "C176") (pin "2") (pinfunction "2_2") (pintype "passive"))
      (node (ref "IC24") (pin "6") (pinfunction "S4_6") (pintype "bidirectional"))
    )
    (net (code "47") (name "Net-(IC25-A)") (class "Default")
      (node (ref "IC25") (pin "1") (pinfunction "A_1") (pintype "input"))
      (node (ref "R63") (pin "2") (pinfunction "2_2") (pintype "passive"))
    )
    (net (code "48") (name "Net-(IC25-C)") (class "Default")
      (node (ref "C183") (pin "2") (pinfunction "2_2") (pintype "passive"))
      (node (ref "IC25") (pin "3") (pinfunction "C_3") (pintype "open_collector"))
    )
    (net (code "49") (name "Net-(IC35-A)") (class "Default")
      (node (ref "IC35") (pin "1") (pinfunction "A_1") (pintype "input"))
      (node (ref "R64") (pin "2") (pinfunction "2_2") (pintype "passive"))
    )
    (net (code "50") (name "Net-(IC57-A)") (class "Default")
      (node (ref "IC57") (pin "1") (pinfunction "A_1") (pintype "input"))
      (node (ref "R209") (pin "2") (pinfunction "2_2") (pintype "passive"))
    )
    (net (code "51") (name "P5V0") (class "Default")
      (node (ref "C103") (pin "2") (pinfunction "2_2") (pintype "passive"))
      (node (ref "C115") (pin "2") (pinfunction "2_2") (pintype "passive"))
      (node (ref "C177") (pin "2") (pinfunction "2_2") (pintype "passive"))
      (node (ref "C89") (pin "2") (pinfunction "2_2") (pintype "passive"))
      (node (ref "IC21") (pin "13") (pinfunction "V+_13") (pintype "power_in"))
      (node (ref "IC22") (pin "13") (pinfunction "V+_13") (pintype "power_in"))
      (node (ref "IC23") (pin "13") (pinfunction "V+_13") (pintype "power_in"))
      (node (ref "IC24") (pin "13") (pinfunction "V+_13") (pintype "power_in"))
    )
    (net (code "52") (name "unconnected-(IC21-N.C.-Pad12)") (class "Default")
      (node (ref "IC21") (pin "12") (pinfunction "N.C._12") (pintype "power_in"))
    )
    (net (code "53") (name "unconnected-(IC22-N.C.-Pad12)") (class "Default")
      (node (ref "IC22") (pin "12") (pinfunction "N.C._12") (pintype "power_in"))
    )
    (net (code "54") (name "unconnected-(IC23-N.C.-Pad12)") (class "Default")
      (node (ref "IC23") (pin "12") (pinfunction "N.C._12") (pintype "power_in"))
    )
    (net (code "55") (name "unconnected-(IC24-N.C.-Pad12)") (class "Default")
      (node (ref "IC24") (pin "12") (pinfunction "N.C._12") (pintype "power_in"))
    )
  )
)
